# pcb.net
KiCad netlist of a schematic drawn in EasyEDA
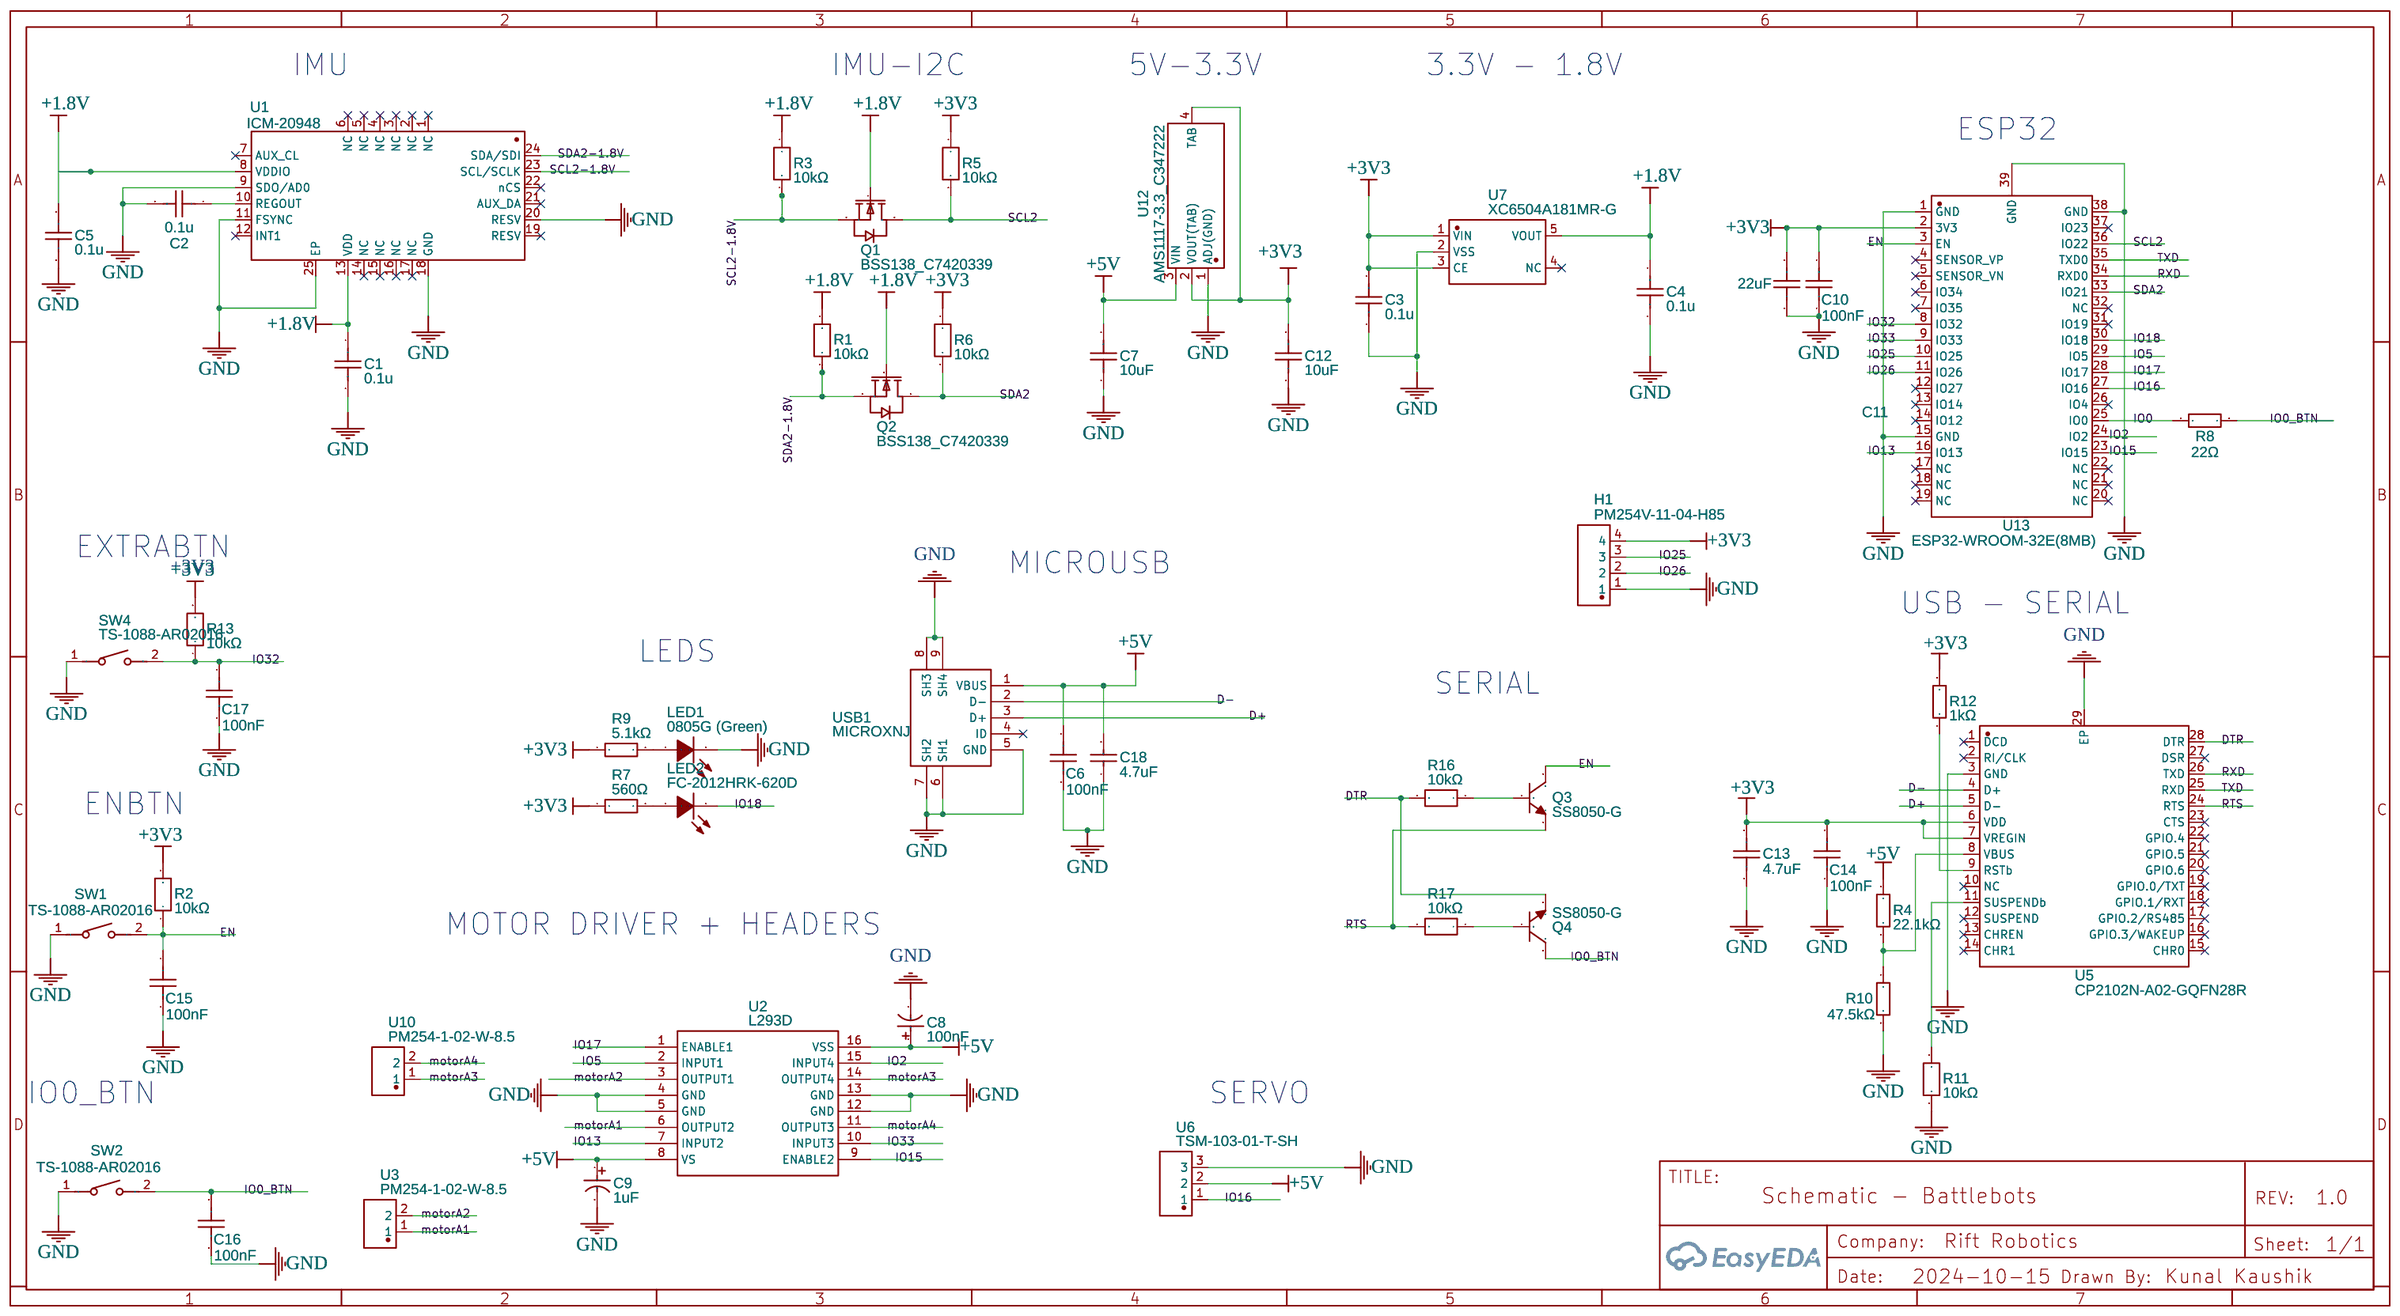
[diagram p0: schematic sheet]

(export (version "E")
  (design (tool "Eeschema 10.0.6"))
  (components
    (comp (ref "C1") (value "0.1u") (libsource (lib "") (part "C_0603_US_1")))
    (comp (ref "C2") (value "0.1u") (libsource (lib "") (part "C_0603_US")))
    (comp (ref "C3") (value "0.1u") (libsource (lib "") (part "C_0603_US_1")))
    (comp (ref "C4") (value "0.1u") (libsource (lib "") (part "C_0603_US_1")))
    (comp (ref "C5") (value "0.1u") (libsource (lib "") (part "C_0603_US_1")))
    (comp (ref "C6")
      (value "100nF")
      (fields
        (field (name "Manufacturer Part") "GCM188R11H104KA42D")
        (field (name "Manufacturer") "muRata(村田)")
      )
      (libsource (lib "") (part "GCM188R11H104KA42D"))
    )
    (comp (ref "C7")
      (value "10uF")
      (fields
        (field (name "Manufacturer Part") "CL05A106MP5NUNC")
        (field (name "Manufacturer") "SAMSUNG(三星)")
      )
      (libsource (lib "") (part "CL05A106MP5NUNC_C315248"))
    )
    (comp (ref "C8")
      (value "100nF")
      (fields
        (field (name "Manufacturer Part") "KS104M050C07RR0VH2FP0")
        (field (name "Manufacturer") "CX(承兴)")
      )
      (libsource (lib "") (part "0.1uF 50V 4*7"))
    )
    (comp (ref "C9")
      (value "1uF")
      (fields
        (field (name "Manufacturer Part") "KF105M050C05RR0VH2FP0")
        (field (name "Manufacturer") "CX(承兴)")
      )
      (libsource (lib "") (part "1uF 50V 4*5"))
    )
    (comp (ref "C10")
      (value "100nF")
      (fields
        (field (name "Manufacturer Part") "GCM188R11H104KA42D")
        (field (name "Manufacturer") "muRata(村田)")
      )
      (libsource (lib "") (part "GCM188R11H104KA42D"))
    )
    (comp (ref "C11")
      (value "22uF")
      (fields
        (field (name "Manufacturer Part") "CL21A226MAYNNNE")
        (field (name "Manufacturer") "SAMSUNG(三星)")
      )
      (libsource (lib "") (part "CL21A226MAYNNNE"))
    )
    (comp (ref "C12")
      (value "10uF")
      (fields
        (field (name "Manufacturer Part") "CL05A106MP5NUNC")
        (field (name "Manufacturer") "SAMSUNG(三星)")
      )
      (libsource (lib "") (part "CL05A106MP5NUNC_C315248"))
    )
    (comp (ref "C13")
      (value "4.7uF")
      (fields
        (field (name "Manufacturer Part") "CL05A475KP5NRNC")
        (field (name "Manufacturer") "SAMSUNG(三星)")
      )
      (libsource (lib "") (part "CL05A475KP5NRNC"))
    )
    (comp (ref "C14")
      (value "100nF")
      (fields
        (field (name "Manufacturer Part") "GCM188R11H104KA42D")
        (field (name "Manufacturer") "muRata(村田)")
      )
      (libsource (lib "") (part "GCM188R11H104KA42D"))
    )
    (comp (ref "C15")
      (value "100nF")
      (fields
        (field (name "Manufacturer Part") "GCM188R11H104KA42D")
        (field (name "Manufacturer") "muRata(村田)")
      )
      (libsource (lib "") (part "GCM188R11H104KA42D"))
    )
    (comp (ref "C16")
      (value "100nF")
      (fields
        (field (name "Manufacturer Part") "GCM188R11H104KA42D")
        (field (name "Manufacturer") "muRata(村田)")
      )
      (libsource (lib "") (part "GCM188R11H104KA42D"))
    )
    (comp (ref "C17")
      (value "100nF")
      (fields
        (field (name "Manufacturer Part") "GCM188R11H104KA42D")
        (field (name "Manufacturer") "muRata(村田)")
      )
      (libsource (lib "") (part "GCM188R11H104KA42D"))
    )
    (comp (ref "C18")
      (value "4.7uF")
      (fields
        (field (name "Manufacturer Part") "CL10A475KP8NNNC")
        (field (name "Manufacturer") "SAMSUNG(三星)")
      )
      (libsource (lib "") (part "CL10A475KP8NNNC"))
    )
    (comp (ref "H1")
      (value "PM254V-11-04-H85")
      (fields (field (name "Manufacturer") "XFCN(兴飞)"))
      (libsource (lib "") (part "PM254V-11-04-H85"))
    )
    (comp (ref "LED1")
      (value "0805G (Green)")
      (fields (field (name "Manufacturer Part") "KT-0805G") (field (name "Manufacturer") "KENTO"))
      (libsource (lib "") (part "0805G (Green)"))
    )
    (comp (ref "LED2")
      (value "FC-2012HRK-620D")
      (fields (field (name "Manufacturer Part") "NCD0805R1") (field (name "Manufacturer") "国星光电"))
      (libsource (lib "") (part "FC-2012HRK-620D"))
    )
    (comp (ref "Q1")
      (value "BSS138_C7420339")
      (fields (field (name "Manufacturer Part") "BSS138") (field (name "Manufacturer") "宏迦橙"))
      (libsource (lib "") (part "BSS138_C7420339"))
    )
    (comp (ref "Q2")
      (value "BSS138_C7420339")
      (fields (field (name "Manufacturer Part") "BSS138") (field (name "Manufacturer") "宏迦橙"))
      (libsource (lib "") (part "BSS138_C7420339"))
    )
    (comp (ref "Q3")
      (value "SS8050-G")
      (fields
        (field (name "Manufacturer Part") "SS8050-G(RANGE:120-200)")
        (field (name "Manufacturer") "CJ(江苏长电/长晶)")
      )
      (libsource (lib "") (part "SS8050-G"))
    )
    (comp (ref "Q4")
      (value "SS8050-G")
      (fields
        (field (name "Manufacturer Part") "SS8050-G(RANGE:120-200)")
        (field (name "Manufacturer") "CJ(江苏长电/长晶)")
      )
      (libsource (lib "") (part "SS8050-G_1"))
    )
    (comp (ref "R1")
      (value "10kΩ")
      (fields (field (name "Manufacturer Part") "SCR0603J10K") (field (name "Manufacturer") "VO(翔胜)"))
      (libsource (lib "") (part "SCR0603J10K"))
    )
    (comp (ref "R2")
      (value "10kΩ")
      (fields (field (name "Manufacturer Part") "SCR0603J10K") (field (name "Manufacturer") "VO(翔胜)"))
      (libsource (lib "") (part "SCR0603J10K"))
    )
    (comp (ref "R3")
      (value "10kΩ")
      (fields (field (name "Manufacturer Part") "SCR0603J10K") (field (name "Manufacturer") "VO(翔胜)"))
      (libsource (lib "") (part "SCR0603J10K_2"))
    )
    (comp (ref "R4")
      (value "22.1kΩ")
      (fields
        (field (name "Manufacturer Part") "0402WGF2212TCE")
        (field (name "Manufacturer") "UNI-ROYAL(厚声)")
      )
      (libsource (lib "") (part "0402WGF2212TCE"))
    )
    (comp (ref "R5")
      (value "10kΩ")
      (fields (field (name "Manufacturer Part") "SCR0603J10K") (field (name "Manufacturer") "VO(翔胜)"))
      (libsource (lib "") (part "SCR0603J10K_2"))
    )
    (comp (ref "R6")
      (value "10kΩ")
      (fields (field (name "Manufacturer Part") "SCR0603J10K") (field (name "Manufacturer") "VO(翔胜)"))
      (libsource (lib "") (part "SCR0603J10K_2"))
    )
    (comp (ref "R7")
      (value "560Ω")
      (fields
        (field (name "Manufacturer Part") "0402WGJ0561TCE")
        (field (name "Manufacturer") "UNI-ROYAL(厚声)")
      )
      (libsource (lib "") (part "0402WGJ0561TCE"))
    )
    (comp (ref "R8")
      (value "22Ω")
      (fields
        (field (name "Manufacturer Part") "0402WGF220JTCE")
        (field (name "Manufacturer") "UNI-ROYAL(厚声)")
      )
      (libsource (lib "") (part "0402WGF220JTCE"))
    )
    (comp (ref "R9")
      (value "5.1kΩ")
      (fields
        (field (name "Manufacturer Part") "0402WGF5101TCE")
        (field (name "Manufacturer") "UNI-ROYAL(厚声)")
      )
      (libsource (lib "") (part "0402WGF5101TCE"))
    )
    (comp (ref "R10")
      (value "47.5kΩ")
      (fields
        (field (name "Manufacturer Part") "0402WGF4752TCE")
        (field (name "Manufacturer") "UNI-ROYAL(厚声)")
      )
      (libsource (lib "") (part "0402WGF4752TCE"))
    )
    (comp (ref "R11")
      (value "10kΩ")
      (fields (field (name "Manufacturer Part") "SCR0603J10K") (field (name "Manufacturer") "VO(翔胜)"))
      (libsource (lib "") (part "SCR0603J10K"))
    )
    (comp (ref "R12")
      (value "1kΩ")
      (fields
        (field (name "Manufacturer Part") "0402WGF1001TCE")
        (field (name "Manufacturer") "UNI-ROYAL(厚声)")
      )
      (libsource (lib "") (part "0402WGF1001TCE"))
    )
    (comp (ref "R13")
      (value "10kΩ")
      (fields (field (name "Manufacturer Part") "SCR0603J10K") (field (name "Manufacturer") "VO(翔胜)"))
      (libsource (lib "") (part "SCR0603J10K"))
    )
    (comp (ref "R16")
      (value "10kΩ")
      (fields (field (name "Manufacturer Part") "SCR0603J10K") (field (name "Manufacturer") "VO(翔胜)"))
      (libsource (lib "") (part "SCR0603J10K_1"))
    )
    (comp (ref "R17")
      (value "10kΩ")
      (fields (field (name "Manufacturer Part") "SCR0603J10K") (field (name "Manufacturer") "VO(翔胜)"))
      (libsource (lib "") (part "SCR0603J10K_1"))
    )
    (comp (ref "SW1")
      (value "TS-1088-AR02016")
      (fields (field (name "Manufacturer") "XUNPU(讯普)"))
      (libsource (lib "") (part "TS-1088-AR02016"))
    )
    (comp (ref "SW2")
      (value "TS-1088-AR02016")
      (fields (field (name "Manufacturer") "XUNPU(讯普)"))
      (libsource (lib "") (part "TS-1088-AR02016"))
    )
    (comp (ref "SW4")
      (value "TS-1088-AR02016")
      (fields (field (name "Manufacturer") "XUNPU(讯普)"))
      (libsource (lib "") (part "TS-1088-AR02016"))
    )
    (comp (ref "U1")
      (value "ICM-20948")
      (fields (field (name "Manufacturer") "TDK InvenSense(应美盛)"))
      (libsource (lib "") (part "ICM-20948"))
    )
    (comp (ref "U2")
      (value "L293D")
      (fields (field (name "Manufacturer") "ST(意法半导体)"))
      (libsource (lib "") (part "L293D"))
    )
    (comp (ref "U3")
      (value "PM254-1-02-W-8.5")
      (fields (field (name "Manufacturer") "HCTL(华灿天禄)"))
      (libsource (lib "") (part "PM254-1-02-W-8.5"))
    )
    (comp (ref "U5")
      (value "CP2102N-A02-GQFN28R")
      (fields (field (name "Manufacturer") "SKYWORKS/SILICON LABS(芯科)"))
      (libsource (lib "") (part "CP2102N-A02-GQFN28R"))
    )
    (comp (ref "U6")
      (value "TSM-103-01-T-SH")
      (fields (field (name "Manufacturer") "SAMTEC"))
      (libsource (lib "") (part "TSM-103-01-T-SH"))
    )
    (comp (ref "U7")
      (value "XC6504A181MR-G")
      (fields (field (name "Manufacturer") "TOREX(特瑞仕)"))
      (libsource (lib "") (part "XC6504A181MR-G"))
    )
    (comp (ref "U10")
      (value "PM254-1-02-W-8.5")
      (fields (field (name "Manufacturer") "HCTL(华灿天禄)"))
      (libsource (lib "") (part "PM254-1-02-W-8.5"))
    )
    (comp (ref "U12")
      (value "AMS1117-3.3_C347222")
      (fields (field (name "Manufacturer Part") "AMS1117-3.3") (field (name "Manufacturer") "UMW(友台半导体)"))
      (libsource (lib "") (part "AMS1117-3.3_C347222"))
    )
    (comp (ref "U13")
      (value "ESP32-WROOM-32E(8MB)")
      (fields
        (field (name "Manufacturer Part") "ESP32-WROOM-32E-N8")
        (field (name "Manufacturer") "ESPRESSIF(乐鑫)")
      )
      (libsource (lib "") (part "ESP32-WROOM-32E(8MB)"))
    )
    (comp (ref "USB1")
      (value "MICROXNJ")
      (fields (field (name "Manufacturer Part") "MicroXNJ") (field (name "Manufacturer") "SHOU HAN(首韩)"))
      (libsource (lib "") (part "MICROXNJ"))
    )
  )
  (nets
    (net (code "1") (name "+1.8V") (class "Default")
      (node (ref "C1") (pin "1") (pinfunction "1_1") (pintype "unspecified"))
      (node (ref "C4") (pin "1") (pinfunction "1_1") (pintype "unspecified"))
      (node (ref "C5") (pin "1") (pinfunction "1_1") (pintype "unspecified"))
      (node (ref "Q1") (pin "1") (pinfunction "G_1") (pintype "unspecified"))
      (node (ref "Q2") (pin "1") (pinfunction "G_1") (pintype "unspecified"))
      (node (ref "R1") (pin "2") (pinfunction "2_2") (pintype "unspecified"))
      (node (ref "R3") (pin "1") (pinfunction "1_1") (pintype "unspecified"))
      (node (ref "U1") (pin "13") (pinfunction "VDD_13") (pintype "unspecified"))
      (node (ref "U1") (pin "8") (pinfunction "VDDIO_8") (pintype "unspecified"))
      (node (ref "U7") (pin "5") (pinfunction "VOUT_5") (pintype "unspecified"))
    )
    (net (code "2") (name "+3V3") (class "Default")
      (node (ref "C10") (pin "1") (pinfunction "1_1") (pintype "unspecified"))
      (node (ref "C11") (pin "2") (pinfunction "2_2") (pintype "unspecified"))
      (node (ref "C12") (pin "2") (pinfunction "2_2") (pintype "unspecified"))
      (node (ref "C13") (pin "2") (pinfunction "2_2") (pintype "unspecified"))
      (node (ref "C14") (pin "1") (pinfunction "1_1") (pintype "unspecified"))
      (node (ref "C3") (pin "1") (pinfunction "1_1") (pintype "unspecified"))
      (node (ref "H1") (pin "4") (pinfunction "4_4") (pintype "unspecified"))
      (node (ref "R12") (pin "2") (pinfunction "2_2") (pintype "input"))
      (node (ref "R13") (pin "2") (pinfunction "2_2") (pintype "unspecified"))
      (node (ref "R2") (pin "2") (pinfunction "2_2") (pintype "unspecified"))
      (node (ref "R5") (pin "1") (pinfunction "1_1") (pintype "unspecified"))
      (node (ref "R6") (pin "1") (pinfunction "1_1") (pintype "unspecified"))
      (node (ref "R7") (pin "1") (pinfunction "1_1") (pintype "input"))
      (node (ref "R9") (pin "1") (pinfunction "1_1") (pintype "input"))
      (node (ref "U12") (pin "2") (pinfunction "VOUT(TAB)_2") (pintype "unspecified"))
      (node (ref "U12") (pin "4") (pinfunction "TAB_4") (pintype "unspecified"))
      (node (ref "U13") (pin "2") (pinfunction "3V3_2") (pintype "unspecified"))
      (node (ref "U5") (pin "6") (pinfunction "VDD_6") (pintype "unspecified"))
      (node (ref "U5") (pin "7") (pinfunction "VREGIN_7") (pintype "unspecified"))
      (node (ref "U7") (pin "1") (pinfunction "VIN_1") (pintype "unspecified"))
      (node (ref "U7") (pin "3") (pinfunction "CE_3") (pintype "unspecified"))
    )
    (net (code "3") (name "+5V") (class "Default")
      (node (ref "C18") (pin "2") (pinfunction "2_2") (pintype "input"))
      (node (ref "C6") (pin "1") (pinfunction "1_1") (pintype "unspecified"))
      (node (ref "C7") (pin "2") (pinfunction "2_2") (pintype "unspecified"))
      (node (ref "C8") (pin "1") (pinfunction "1_1") (pintype "input"))
      (node (ref "C9") (pin "1") (pinfunction "1_1") (pintype "input"))
      (node (ref "R4") (pin "2") (pinfunction "2_2") (pintype "input"))
      (node (ref "U12") (pin "3") (pinfunction "VIN_3") (pintype "unspecified"))
      (node (ref "U2") (pin "16") (pinfunction "VSS_16") (pintype "unspecified"))
      (node (ref "U2") (pin "8") (pinfunction "VS_8") (pintype "unspecified"))
      (node (ref "U6") (pin "2") (pinfunction "2_2") (pintype "unspecified"))
      (node (ref "USB1") (pin "1") (pinfunction "VBUS_1") (pintype "unspecified"))
    )
    (net (code "4") (name "/D+") (class "Default")
      (node (ref "U5") (pin "5") (pinfunction "D-_5") (pintype "unspecified"))
      (node (ref "USB1") (pin "3") (pinfunction "D+_3") (pintype "unspecified"))
    )
    (net (code "5") (name "/D-") (class "Default")
      (node (ref "U5") (pin "4") (pinfunction "D+_4") (pintype "unspecified"))
      (node (ref "USB1") (pin "2") (pinfunction "D-_2") (pintype "unspecified"))
    )
    (net (code "6") (name "/DTR") (class "Default")
      (node (ref "Q4") (pin "2") (pinfunction "E_2") (pintype "input"))
      (node (ref "R16") (pin "2") (pinfunction "2_2") (pintype "unspecified"))
      (node (ref "U5") (pin "28") (pinfunction "DTR_28") (pintype "unspecified"))
    )
    (net (code "7") (name "/EN") (class "Default")
      (node (ref "C15") (pin "1") (pinfunction "1_1") (pintype "unspecified"))
      (node (ref "Q3") (pin "3") (pinfunction "C_3") (pintype "input"))
      (node (ref "R2") (pin "1") (pinfunction "1_1") (pintype "unspecified"))
      (node (ref "SW1") (pin "2") (pinfunction "2_2") (pintype "unspecified"))
      (node (ref "U13") (pin "3") (pinfunction "EN_3") (pintype "unspecified"))
    )
    (net (code "8") (name "/IO0") (class "Default")
      (node (ref "R8") (pin "1") (pinfunction "1_1") (pintype "input"))
      (node (ref "U13") (pin "25") (pinfunction "IO0_25") (pintype "unspecified"))
    )
    (net (code "9") (name "/IO0_BTN") (class "Default")
      (node (ref "C16") (pin "1") (pinfunction "1_1") (pintype "unspecified"))
      (node (ref "Q4") (pin "3") (pinfunction "C_3") (pintype "input"))
      (node (ref "R8") (pin "2") (pinfunction "2_2") (pintype "input"))
      (node (ref "SW2") (pin "2") (pinfunction "2_2") (pintype "unspecified"))
    )
    (net (code "10") (name "/IO2") (class "Default")
      (node (ref "U13") (pin "24") (pinfunction "IO2_24") (pintype "unspecified"))
      (node (ref "U2") (pin "15") (pinfunction "INPUT4_15") (pintype "unspecified"))
    )
    (net (code "11") (name "/IO5") (class "Default")
      (node (ref "U13") (pin "29") (pinfunction "IO5_29") (pintype "unspecified"))
      (node (ref "U2") (pin "2") (pinfunction "INPUT1_2") (pintype "unspecified"))
    )
    (net (code "12") (name "/IO13") (class "Default")
      (node (ref "U13") (pin "16") (pinfunction "IO13_16") (pintype "unspecified"))
      (node (ref "U2") (pin "7") (pinfunction "INPUT2_7") (pintype "unspecified"))
    )
    (net (code "13") (name "/IO15") (class "Default")
      (node (ref "U13") (pin "23") (pinfunction "IO15_23") (pintype "unspecified"))
      (node (ref "U2") (pin "9") (pinfunction "ENABLE2_9") (pintype "unspecified"))
    )
    (net (code "14") (name "/IO16") (class "Default")
      (node (ref "U13") (pin "27") (pinfunction "IO16_27") (pintype "unspecified"))
      (node (ref "U6") (pin "1") (pinfunction "1_1") (pintype "unspecified"))
    )
    (net (code "15") (name "/IO17") (class "Default")
      (node (ref "U13") (pin "28") (pinfunction "IO17_28") (pintype "unspecified"))
      (node (ref "U2") (pin "1") (pinfunction "ENABLE1_1") (pintype "unspecified"))
    )
    (net (code "16") (name "/IO18") (class "Default")
      (node (ref "LED2") (pin "2") (pinfunction "-_2") (pintype "unspecified"))
      (node (ref "U13") (pin "30") (pinfunction "IO18_30") (pintype "unspecified"))
    )
    (net (code "17") (name "/IO25") (class "Default")
      (node (ref "H1") (pin "3") (pinfunction "3_3") (pintype "unspecified"))
      (node (ref "U13") (pin "10") (pinfunction "IO25_10") (pintype "unspecified"))
    )
    (net (code "18") (name "/IO26") (class "Default")
      (node (ref "H1") (pin "2") (pinfunction "2_2") (pintype "unspecified"))
      (node (ref "U13") (pin "11") (pinfunction "IO26_11") (pintype "unspecified"))
    )
    (net (code "19") (name "/IO32") (class "Default")
      (node (ref "C17") (pin "1") (pinfunction "1_1") (pintype "unspecified"))
      (node (ref "R13") (pin "1") (pinfunction "1_1") (pintype "unspecified"))
      (node (ref "SW4") (pin "2") (pinfunction "2_2") (pintype "unspecified"))
      (node (ref "U13") (pin "8") (pinfunction "IO32_8") (pintype "unspecified"))
    )
    (net (code "20") (name "/IO33") (class "Default")
      (node (ref "U13") (pin "9") (pinfunction "IO33_9") (pintype "unspecified"))
      (node (ref "U2") (pin "10") (pinfunction "INPUT3_10") (pintype "unspecified"))
    )
    (net (code "21") (name "/RTS") (class "Default")
      (node (ref "Q3") (pin "2") (pinfunction "E_2") (pintype "input"))
      (node (ref "R17") (pin "2") (pinfunction "2_2") (pintype "unspecified"))
      (node (ref "U5") (pin "24") (pinfunction "RTS_24") (pintype "unspecified"))
    )
    (net (code "22") (name "/RXD") (class "Default")
      (node (ref "U13") (pin "34") (pinfunction "RXD0_34") (pintype "unspecified"))
      (node (ref "U5") (pin "26") (pinfunction "TXD_26") (pintype "unspecified"))
    )
    (net (code "23") (name "/SCL2") (class "Default")
      (node (ref "Q1") (pin "3") (pinfunction "D_3") (pintype "unspecified"))
      (node (ref "R5") (pin "2") (pinfunction "2_2") (pintype "unspecified"))
      (node (ref "U13") (pin "36") (pinfunction "IO22_36") (pintype "unspecified"))
    )
    (net (code "24") (name "/SCL2-1.8V") (class "Default")
      (node (ref "Q1") (pin "2") (pinfunction "S_2") (pintype "unspecified"))
      (node (ref "R3") (pin "2") (pinfunction "2_2") (pintype "unspecified"))
      (node (ref "U1") (pin "23") (pinfunction "SCL/SCLK_23") (pintype "unspecified"))
    )
    (net (code "25") (name "/SDA2") (class "Default")
      (node (ref "Q2") (pin "3") (pinfunction "D_3") (pintype "unspecified"))
      (node (ref "R6") (pin "2") (pinfunction "2_2") (pintype "unspecified"))
      (node (ref "U13") (pin "33") (pinfunction "IO21_33") (pintype "unspecified"))
    )
    (net (code "26") (name "/SDA2-1.8V") (class "Default")
      (node (ref "Q2") (pin "2") (pinfunction "S_2") (pintype "unspecified"))
      (node (ref "R1") (pin "1") (pinfunction "1_1") (pintype "unspecified"))
      (node (ref "U1") (pin "24") (pinfunction "SDA/SDI_24") (pintype "unspecified"))
    )
    (net (code "27") (name "/TXD") (class "Default")
      (node (ref "U13") (pin "35") (pinfunction "TXD0_35") (pintype "unspecified"))
      (node (ref "U5") (pin "25") (pinfunction "RXD_25") (pintype "unspecified"))
    )
    (net (code "28") (name "/motorA1") (class "Default")
      (node (ref "U2") (pin "6") (pinfunction "OUTPUT2_6") (pintype "unspecified"))
      (node (ref "U3") (pin "1") (pinfunction "1_1") (pintype "unspecified"))
    )
    (net (code "29") (name "/motorA2") (class "Default")
      (node (ref "U2") (pin "3") (pinfunction "OUTPUT1_3") (pintype "unspecified"))
      (node (ref "U3") (pin "2") (pinfunction "2_2") (pintype "unspecified"))
    )
    (net (code "30") (name "/motorA3") (class "Default")
      (node (ref "U10") (pin "1") (pinfunction "1_1") (pintype "unspecified"))
      (node (ref "U2") (pin "14") (pinfunction "OUTPUT4_14") (pintype "unspecified"))
    )
    (net (code "31") (name "/motorA4") (class "Default")
      (node (ref "U10") (pin "2") (pinfunction "2_2") (pintype "unspecified"))
      (node (ref "U2") (pin "11") (pinfunction "OUTPUT3_11") (pintype "unspecified"))
    )
    (net (code "32") (name "GND") (class "Default")
      (node (ref "C1") (pin "2") (pinfunction "2_2") (pintype "unspecified"))
      (node (ref "C10") (pin "2") (pinfunction "2_2") (pintype "unspecified"))
      (node (ref "C11") (pin "1") (pinfunction "1_1") (pintype "unspecified"))
      (node (ref "C12") (pin "1") (pinfunction "1_1") (pintype "unspecified"))
      (node (ref "C13") (pin "1") (pinfunction "1_1") (pintype "unspecified"))
      (node (ref "C14") (pin "2") (pinfunction "2_2") (pintype "unspecified"))
      (node (ref "C15") (pin "2") (pinfunction "2_2") (pintype "unspecified"))
      (node (ref "C16") (pin "2") (pinfunction "2_2") (pintype "unspecified"))
      (node (ref "C17") (pin "2") (pinfunction "2_2") (pintype "unspecified"))
      (node (ref "C18") (pin "1") (pinfunction "1_1") (pintype "input"))
      (node (ref "C2") (pin "2") (pinfunction "2_2") (pintype "unspecified"))
      (node (ref "C3") (pin "2") (pinfunction "2_2") (pintype "unspecified"))
      (node (ref "C4") (pin "2") (pinfunction "2_2") (pintype "unspecified"))
      (node (ref "C5") (pin "2") (pinfunction "2_2") (pintype "unspecified"))
      (node (ref "C6") (pin "2") (pinfunction "2_2") (pintype "unspecified"))
      (node (ref "C7") (pin "1") (pinfunction "1_1") (pintype "unspecified"))
      (node (ref "C8") (pin "2") (pinfunction "2_2") (pintype "input"))
      (node (ref "C9") (pin "2") (pinfunction "2_2") (pintype "input"))
      (node (ref "H1") (pin "1") (pinfunction "1_1") (pintype "unspecified"))
      (node (ref "LED1") (pin "2") (pinfunction "K_2") (pintype "unspecified"))
      (node (ref "R10") (pin "2") (pinfunction "2_2") (pintype "input"))
      (node (ref "R11") (pin "1") (pinfunction "1_1") (pintype "unspecified"))
      (node (ref "SW1") (pin "1") (pinfunction "1_1") (pintype "unspecified"))
      (node (ref "SW2") (pin "1") (pinfunction "1_1") (pintype "unspecified"))
      (node (ref "SW4") (pin "1") (pinfunction "1_1") (pintype "unspecified"))
      (node (ref "U1") (pin "11") (pinfunction "FSYNC_11") (pintype "unspecified"))
      (node (ref "U1") (pin "18") (pinfunction "GND_18") (pintype "unspecified"))
      (node (ref "U1") (pin "20") (pinfunction "RESV_20") (pintype "unspecified"))
      (node (ref "U1") (pin "25") (pinfunction "EP_25") (pintype "unspecified"))
      (node (ref "U1") (pin "9") (pinfunction "SDO/AD0_9") (pintype "unspecified"))
      (node (ref "U12") (pin "1") (pinfunction "ADJ(GND)_1") (pintype "unspecified"))
      (node (ref "U13") (pin "1") (pinfunction "GND_1") (pintype "unspecified"))
      (node (ref "U13") (pin "15") (pinfunction "GND_15") (pintype "unspecified"))
      (node (ref "U13") (pin "38") (pinfunction "GND_38") (pintype "unspecified"))
      (node (ref "U13") (pin "39") (pinfunction "GND_39") (pintype "unspecified"))
      (node (ref "U2") (pin "12") (pinfunction "GND_12") (pintype "unspecified"))
      (node (ref "U2") (pin "13") (pinfunction "GND_13") (pintype "unspecified"))
      (node (ref "U2") (pin "4") (pinfunction "GND_4") (pintype "unspecified"))
      (node (ref "U2") (pin "5") (pinfunction "GND_5") (pintype "unspecified"))
      (node (ref "U5") (pin "29") (pinfunction "EP_29") (pintype "unspecified"))
      (node (ref "U5") (pin "3") (pinfunction "GND_3") (pintype "unspecified"))
      (node (ref "U6") (pin "3") (pinfunction "3_3") (pintype "unspecified"))
      (node (ref "U7") (pin "2") (pinfunction "VSS_2") (pintype "unspecified"))
      (node (ref "USB1") (pin "5") (pinfunction "GND_5") (pintype "unspecified"))
      (node (ref "USB1") (pin "6") (pinfunction "SH1_6") (pintype "unspecified"))
      (node (ref "USB1") (pin "7") (pinfunction "SH2_7") (pintype "unspecified"))
      (node (ref "USB1") (pin "8") (pinfunction "SH3_8") (pintype "unspecified"))
      (node (ref "USB1") (pin "9") (pinfunction "SH4_9") (pintype "unspecified"))
    )
    (net (code "33") (name "Net-(LED1-A)") (class "Default")
      (node (ref "LED1") (pin "1") (pinfunction "A_1") (pintype "unspecified"))
      (node (ref "R9") (pin "2") (pinfunction "2_2") (pintype "input"))
    )
    (net (code "34") (name "Net-(LED2-+)") (class "Default")
      (node (ref "LED2") (pin "1") (pinfunction "+_1") (pintype "unspecified"))
      (node (ref "R7") (pin "2") (pinfunction "2_2") (pintype "input"))
    )
    (net (code "35") (name "Net-(Q3-B)") (class "Default")
      (node (ref "Q3") (pin "1") (pinfunction "B_1") (pintype "input"))
      (node (ref "R16") (pin "1") (pinfunction "1_1") (pintype "unspecified"))
    )
    (net (code "36") (name "Net-(Q4-B)") (class "Default")
      (node (ref "Q4") (pin "1") (pinfunction "B_1") (pintype "input"))
      (node (ref "R17") (pin "1") (pinfunction "1_1") (pintype "unspecified"))
    )
    (net (code "37") (name "Net-(U1-REGOUT)") (class "Default")
      (node (ref "C2") (pin "1") (pinfunction "1_1") (pintype "unspecified"))
      (node (ref "U1") (pin "10") (pinfunction "REGOUT_10") (pintype "unspecified"))
    )
    (net (code "38") (name "Net-(U5-RSTb)") (class "Default")
      (node (ref "R12") (pin "1") (pinfunction "1_1") (pintype "input"))
      (node (ref "U5") (pin "9") (pinfunction "RSTb_9") (pintype "unspecified"))
    )
    (net (code "39") (name "Net-(U5-SUSPENDb)") (class "Default")
      (node (ref "R11") (pin "2") (pinfunction "2_2") (pintype "unspecified"))
      (node (ref "U5") (pin "11") (pinfunction "SUSPENDb_11") (pintype "unspecified"))
    )
    (net (code "40") (name "Net-(U5-VBUS)") (class "Default")
      (node (ref "R10") (pin "1") (pinfunction "1_1") (pintype "input"))
      (node (ref "R4") (pin "1") (pinfunction "1_1") (pintype "input"))
      (node (ref "U5") (pin "8") (pinfunction "VBUS_8") (pintype "unspecified"))
    )
    (net (code "41") (name "unconnected-(U1-AUX_CL-Pad7)") (class "Default")
      (node (ref "U1") (pin "7") (pinfunction "AUX_CL_7") (pintype "unspecified+no_connect"))
    )
    (net (code "42") (name "unconnected-(U1-AUX_DA-Pad21)") (class "Default")
      (node (ref "U1") (pin "21") (pinfunction "AUX_DA_21") (pintype "unspecified+no_connect"))
    )
    (net (code "43") (name "unconnected-(U1-INT1-Pad12)") (class "Default")
      (node (ref "U1") (pin "12") (pinfunction "INT1_12") (pintype "unspecified+no_connect"))
    )
    (net (code "44") (name "unconnected-(U1-NC-Pad1)") (class "Default")
      (node (ref "U1") (pin "1") (pinfunction "NC_1") (pintype "unspecified+no_connect"))
    )
    (net (code "45") (name "unconnected-(U1-NC-Pad2)") (class "Default")
      (node (ref "U1") (pin "2") (pinfunction "NC_2") (pintype "unspecified+no_connect"))
    )
    (net (code "46") (name "unconnected-(U1-NC-Pad3)") (class "Default")
      (node (ref "U1") (pin "3") (pinfunction "NC_3") (pintype "unspecified+no_connect"))
    )
    (net (code "47") (name "unconnected-(U1-NC-Pad4)") (class "Default")
      (node (ref "U1") (pin "4") (pinfunction "NC_4") (pintype "unspecified+no_connect"))
    )
    (net (code "48") (name "unconnected-(U1-NC-Pad5)") (class "Default")
      (node (ref "U1") (pin "5") (pinfunction "NC_5") (pintype "unspecified+no_connect"))
    )
    (net (code "49") (name "unconnected-(U1-NC-Pad6)") (class "Default")
      (node (ref "U1") (pin "6") (pinfunction "NC_6") (pintype "unspecified+no_connect"))
    )
    (net (code "50") (name "unconnected-(U1-NC-Pad14)") (class "Default")
      (node (ref "U1") (pin "14") (pinfunction "NC_14") (pintype "unspecified+no_connect"))
    )
    (net (code "51") (name "unconnected-(U1-NC-Pad15)") (class "Default")
      (node (ref "U1") (pin "15") (pinfunction "NC_15") (pintype "unspecified+no_connect"))
    )
    (net (code "52") (name "unconnected-(U1-NC-Pad16)") (class "Default")
      (node (ref "U1") (pin "16") (pinfunction "NC_16") (pintype "unspecified+no_connect"))
    )
    (net (code "53") (name "unconnected-(U1-NC-Pad17)") (class "Default")
      (node (ref "U1") (pin "17") (pinfunction "NC_17") (pintype "unspecified+no_connect"))
    )
    (net (code "54") (name "unconnected-(U1-RESV-Pad19)") (class "Default")
      (node (ref "U1") (pin "19") (pinfunction "RESV_19") (pintype "unspecified+no_connect"))
    )
    (net (code "55") (name "unconnected-(U1-nCS-Pad22)") (class "Default")
      (node (ref "U1") (pin "22") (pinfunction "nCS_22") (pintype "unspecified+no_connect"))
    )
    (net (code "56") (name "unconnected-(U5-CHR0-Pad15)") (class "Default")
      (node (ref "U5") (pin "15") (pinfunction "CHR0_15") (pintype "unspecified+no_connect"))
    )
    (net (code "57") (name "unconnected-(U5-CHR1-Pad14)") (class "Default")
      (node (ref "U5") (pin "14") (pinfunction "CHR1_14") (pintype "unspecified+no_connect"))
    )
    (net (code "58") (name "unconnected-(U5-CHREN-Pad13)") (class "Default")
      (node (ref "U5") (pin "13") (pinfunction "CHREN_13") (pintype "unspecified+no_connect"))
    )
    (net (code "59") (name "unconnected-(U5-CTS-Pad23)") (class "Default")
      (node (ref "U5") (pin "23") (pinfunction "CTS_23") (pintype "unspecified+no_connect"))
    )
    (net (code "60") (name "unconnected-(U5-DCD-Pad1)") (class "Default")
      (node (ref "U5") (pin "1") (pinfunction "DCD_1") (pintype "unspecified+no_connect"))
    )
    (net (code "61") (name "unconnected-(U5-DSR-Pad27)") (class "Default")
      (node (ref "U5") (pin "27") (pinfunction "DSR_27") (pintype "unspecified+no_connect"))
    )
    (net (code "62") (name "unconnected-(U5-GPIO.0{slash}TXT-Pad19)") (class "Default")
      (node (ref "U5") (pin "19") (pinfunction "GPIO.0/TXT_19") (pintype "unspecified+no_connect"))
    )
    (net (code "63") (name "unconnected-(U5-GPIO.1{slash}RXT-Pad18)") (class "Default")
      (node (ref "U5") (pin "18") (pinfunction "GPIO.1/RXT_18") (pintype "unspecified+no_connect"))
    )
    (net (code "64") (name "unconnected-(U5-GPIO.2{slash}RS485-Pad17)") (class "Default")
      (node (ref "U5") (pin "17") (pinfunction "GPIO.2/RS485_17") (pintype "unspecified+no_connect"))
    )
    (net (code "65") (name "unconnected-(U5-GPIO.3{slash}WAKEUP-Pad16)") (class "Default")
      (node (ref "U5") (pin "16") (pinfunction "GPIO.3/WAKEUP_16") (pintype "unspecified+no_connect"))
    )
    (net (code "66") (name "unconnected-(U5-GPIO.4-Pad22)") (class "Default")
      (node (ref "U5") (pin "22") (pinfunction "GPIO.4_22") (pintype "unspecified+no_connect"))
    )
    (net (code "67") (name "unconnected-(U5-GPIO.5-Pad21)") (class "Default")
      (node (ref "U5") (pin "21") (pinfunction "GPIO.5_21") (pintype "unspecified+no_connect"))
    )
    (net (code "68") (name "unconnected-(U5-GPIO.6-Pad20)") (class "Default")
      (node (ref "U5") (pin "20") (pinfunction "GPIO.6_20") (pintype "unspecified+no_connect"))
    )
    (net (code "69") (name "unconnected-(U5-NC-Pad10)") (class "Default")
      (node (ref "U5") (pin "10") (pinfunction "NC_10") (pintype "unspecified+no_connect"))
    )
    (net (code "70") (name "unconnected-(U5-RI{slash}CLK-Pad2)") (class "Default")
      (node (ref "U5") (pin "2") (pinfunction "RI/CLK_2") (pintype "unspecified+no_connect"))
    )
    (net (code "71") (name "unconnected-(U5-SUSPEND-Pad12)") (class "Default")
      (node (ref "U5") (pin "12") (pinfunction "SUSPEND_12") (pintype "unspecified+no_connect"))
    )
    (net (code "72") (name "unconnected-(U7-NC-Pad4)") (class "Default")
      (node (ref "U7") (pin "4") (pinfunction "NC_4") (pintype "unspecified+no_connect"))
    )
    (net (code "73") (name "unconnected-(U13-IO4-Pad26)") (class "Default")
      (node (ref "U13") (pin "26") (pinfunction "IO4_26") (pintype "unspecified+no_connect"))
    )
    (net (code "74") (name "unconnected-(U13-IO12-Pad14)") (class "Default")
      (node (ref "U13") (pin "14") (pinfunction "IO12_14") (pintype "unspecified+no_connect"))
    )
    (net (code "75") (name "unconnected-(U13-IO14-Pad13)") (class "Default")
      (node (ref "U13") (pin "13") (pinfunction "IO14_13") (pintype "unspecified+no_connect"))
    )
    (net (code "76") (name "unconnected-(U13-IO19-Pad31)") (class "Default")
      (node (ref "U13") (pin "31") (pinfunction "IO19_31") (pintype "unspecified+no_connect"))
    )
    (net (code "77") (name "unconnected-(U13-IO23-Pad37)") (class "Default")
      (node (ref "U13") (pin "37") (pinfunction "IO23_37") (pintype "unspecified+no_connect"))
    )
    (net (code "78") (name "unconnected-(U13-IO27-Pad12)") (class "Default")
      (node (ref "U13") (pin "12") (pinfunction "IO27_12") (pintype "unspecified+no_connect"))
    )
    (net (code "79") (name "unconnected-(U13-IO34-Pad6)") (class "Default")
      (node (ref "U13") (pin "6") (pinfunction "IO34_6") (pintype "unspecified+no_connect"))
    )
    (net (code "80") (name "unconnected-(U13-IO35-Pad7)") (class "Default")
      (node (ref "U13") (pin "7") (pinfunction "IO35_7") (pintype "unspecified+no_connect"))
    )
    (net (code "81") (name "unconnected-(U13-NC-Pad17)") (class "Default")
      (node (ref "U13") (pin "17") (pinfunction "NC_17") (pintype "unspecified+no_connect"))
    )
    (net (code "82") (name "unconnected-(U13-NC-Pad18)") (class "Default")
      (node (ref "U13") (pin "18") (pinfunction "NC_18") (pintype "unspecified+no_connect"))
    )
    (net (code "83") (name "unconnected-(U13-NC-Pad19)") (class "Default")
      (node (ref "U13") (pin "19") (pinfunction "NC_19") (pintype "unspecified+no_connect"))
    )
    (net (code "84") (name "unconnected-(U13-NC-Pad20)") (class "Default")
      (node (ref "U13") (pin "20") (pinfunction "NC_20") (pintype "unspecified+no_connect"))
    )
    (net (code "85") (name "unconnected-(U13-NC-Pad21)") (class "Default")
      (node (ref "U13") (pin "21") (pinfunction "NC_21") (pintype "unspecified+no_connect"))
    )
    (net (code "86") (name "unconnected-(U13-NC-Pad22)") (class "Default")
      (node (ref "U13") (pin "22") (pinfunction "NC_22") (pintype "unspecified+no_connect"))
    )
    (net (code "87") (name "unconnected-(U13-NC-Pad32)") (class "Default")
      (node (ref "U13") (pin "32") (pinfunction "NC_32") (pintype "unspecified+no_connect"))
    )
    (net (code "88") (name "unconnected-(U13-SENSOR_VN-Pad5)") (class "Default")
      (node (ref "U13") (pin "5") (pinfunction "SENSOR_VN_5") (pintype "unspecified+no_connect"))
    )
    (net (code "89") (name "unconnected-(U13-SENSOR_VP-Pad4)") (class "Default")
      (node (ref "U13") (pin "4") (pinfunction "SENSOR_VP_4") (pintype "unspecified+no_connect"))
    )
    (net (code "90") (name "unconnected-(USB1-ID-Pad4)") (class "Default")
      (node (ref "USB1") (pin "4") (pinfunction "ID_4") (pintype "unspecified+no_connect"))
    )
  )
)
